# ui_conn.net
KiCad netlist of a schematic drawn in Altium Designer
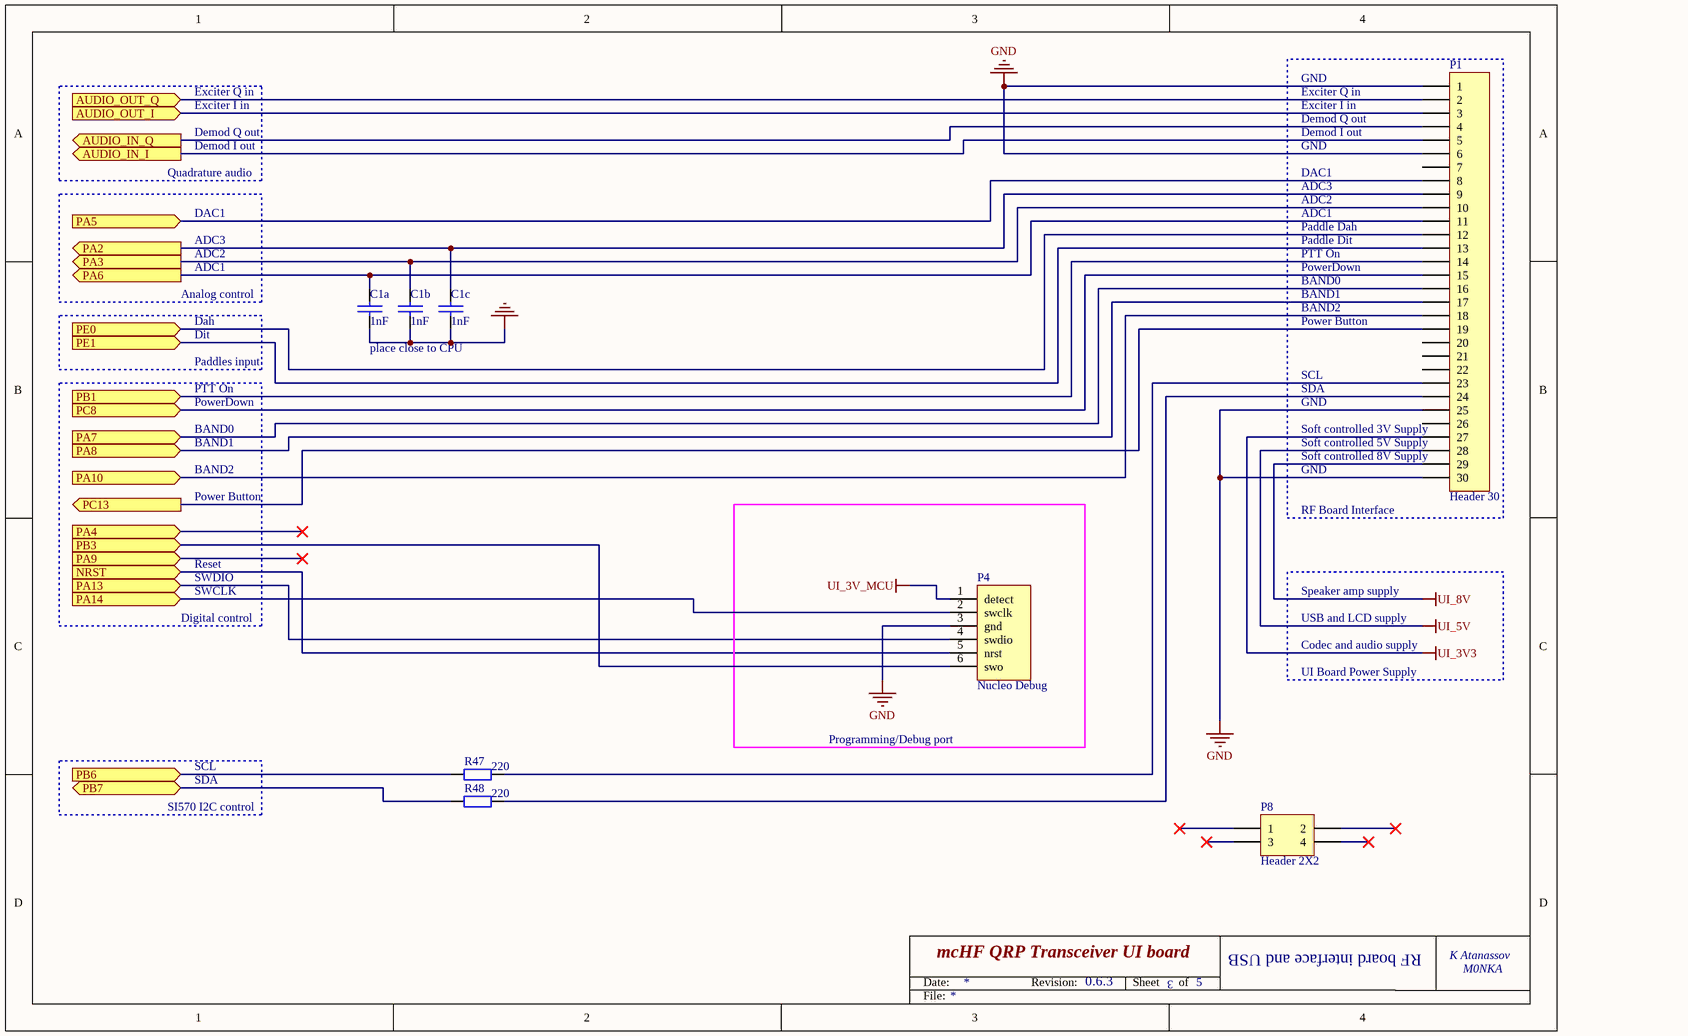
[diagram p0: ui_conn.SchDoc]

(export (version "E")
  (design (tool "Eeschema 10.0.6"))
  (components
    (comp (ref "C1a")
      (value "1nF")
      (footprint "0805-Pro")
      (description "Capacitor")
      (libsource (lib "mcHF_ui") (part "CAP"))
    )
    (comp (ref "C1b")
      (value "1nF")
      (footprint "0805-Pro")
      (description "Capacitor")
      (libsource (lib "mcHF_ui") (part "CAP"))
    )
    (comp (ref "C1c")
      (value "1nF")
      (footprint "0805-Pro")
      (description "Capacitor")
      (libsource (lib "mcHF_ui") (part "CAP"))
    )
    (comp (ref "P1")
      (value "Header 30")
      (footprint "HDR1X30")
      (description "Header, 30-Pin")
      (libsource (lib "mcHF_ui") (part "Header 30"))
    )
    (comp (ref "P4")
      (value "Nucleo Debug")
      (footprint "HDR1X6")
      (description "ST Nucleo 6 pin header")
      (libsource (lib "mcHFpro_logic") (part "Nucleo_6"))
    )
    (comp (ref "P8")
      (value "Header 2X2")
      (footprint "HDR2X2")
      (description "Header, 2-Pin, Dual row")
      (fields (field (name "PUBLISHER") "Altium Limited"))
      (libsource (lib "Miscellaneous Connectors") (part "Header 2X2"))
    )
    (comp (ref "R47")
      (value "220")
      (footprint "0805-Pro")
      (description "Resistor")
      (libsource (lib "mcHF_ui") (part "RES"))
    )
    (comp (ref "R48")
      (value "220")
      (footprint "0805-Pro")
      (description "Resistor")
      (libsource (lib "mcHF_ui") (part "RES"))
    )
  )
  (nets
    (net (code "1") (name "/AUDIO_IN_I") (class "Default")
      (node (ref "P1") (pin "5") (pinfunction "5_5") (pintype "passive"))
    )
    (net (code "2") (name "/AUDIO_IN_Q") (class "Default")
      (node (ref "P1") (pin "4") (pinfunction "4_4") (pintype "passive"))
    )
    (net (code "3") (name "/AUDIO_OUT_I") (class "Default")
      (node (ref "P1") (pin "3") (pinfunction "3_3") (pintype "passive"))
    )
    (net (code "4") (name "/AUDIO_OUT_Q") (class "Default")
      (node (ref "P1") (pin "2") (pinfunction "2_2") (pintype "passive"))
    )
    (net (code "5") (name "/NRST") (class "Default")
      (node (ref "P4") (pin "5") (pinfunction "nrst_5") (pintype "passive"))
    )
    (net (code "6") (name "/PA2") (class "Default")
      (node (ref "C1c") (pin "1") (pinfunction "1_1") (pintype "passive"))
      (node (ref "P1") (pin "9") (pinfunction "9_9") (pintype "passive"))
    )
    (net (code "7") (name "/PA3") (class "Default")
      (node (ref "C1b") (pin "1") (pinfunction "1_1") (pintype "passive"))
      (node (ref "P1") (pin "10") (pinfunction "10_10") (pintype "passive"))
    )
    (net (code "9") (name "/PA5") (class "Default")
      (node (ref "P1") (pin "8") (pinfunction "8_8") (pintype "passive"))
    )
    (net (code "10") (name "/PA6") (class "Default")
      (node (ref "C1a") (pin "1") (pinfunction "1_1") (pintype "passive"))
      (node (ref "P1") (pin "11") (pinfunction "11_11") (pintype "passive"))
    )
    (net (code "11") (name "/PA7") (class "Default")
      (node (ref "P1") (pin "16") (pinfunction "16_16") (pintype "passive"))
    )
    (net (code "12") (name "/PA8") (class "Default")
      (node (ref "P1") (pin "17") (pinfunction "17_17") (pintype "passive"))
    )
    (net (code "14") (name "/PA10") (class "Default")
      (node (ref "P1") (pin "18") (pinfunction "18_18") (pintype "passive"))
    )
    (net (code "15") (name "/PA13") (class "Default")
      (node (ref "P4") (pin "4") (pinfunction "swdio_4") (pintype "passive"))
    )
    (net (code "16") (name "/PA14") (class "Default")
      (node (ref "P4") (pin "2") (pinfunction "swclk_2") (pintype "passive"))
    )
    (net (code "17") (name "/PB1") (class "Default")
      (node (ref "P1") (pin "14") (pinfunction "14_14") (pintype "passive"))
    )
    (net (code "18") (name "/PB3") (class "Default")
      (node (ref "P4") (pin "6") (pinfunction "swo_6") (pintype "passive"))
    )
    (net (code "19") (name "/PB6") (class "Default")
      (node (ref "R47") (pin "1") (pinfunction "1_1") (pintype "passive"))
    )
    (net (code "20") (name "/PB7") (class "Default")
      (node (ref "R48") (pin "1") (pinfunction "1_1") (pintype "passive"))
    )
    (net (code "21") (name "/PC8") (class "Default")
      (node (ref "P1") (pin "15") (pinfunction "15_15") (pintype "passive"))
    )
    (net (code "22") (name "/PC13") (class "Default")
      (node (ref "P1") (pin "19") (pinfunction "19_19") (pintype "passive"))
    )
    (net (code "23") (name "/PE0") (class "Default")
      (node (ref "P1") (pin "12") (pinfunction "12_12") (pintype "passive"))
    )
    (net (code "24") (name "/PE1") (class "Default")
      (node (ref "P1") (pin "13") (pinfunction "13_13") (pintype "passive"))
    )
    (net (code "25") (name "GND") (class "Default")
      (node (ref "C1a") (pin "2") (pinfunction "2_2") (pintype "passive"))
      (node (ref "C1b") (pin "2") (pinfunction "2_2") (pintype "passive"))
      (node (ref "C1c") (pin "2") (pinfunction "2_2") (pintype "passive"))
      (node (ref "P1") (pin "1") (pinfunction "1_1") (pintype "passive"))
      (node (ref "P1") (pin "25") (pinfunction "25_25") (pintype "passive"))
      (node (ref "P1") (pin "30") (pinfunction "30_30") (pintype "passive"))
      (node (ref "P1") (pin "6") (pinfunction "6_6") (pintype "passive"))
      (node (ref "P4") (pin "3") (pinfunction "gnd_3") (pintype "passive"))
    )
    (net (code "26") (name "Net-(P1-Pad23)") (class "Default")
      (node (ref "P1") (pin "23") (pinfunction "23_23") (pintype "passive"))
      (node (ref "R47") (pin "2") (pinfunction "2_2") (pintype "passive"))
    )
    (net (code "27") (name "Net-(P1-Pad24)") (class "Default")
      (node (ref "P1") (pin "24") (pinfunction "24_24") (pintype "passive"))
      (node (ref "R48") (pin "2") (pinfunction "2_2") (pintype "passive"))
    )
    (net (code "28") (name "UI_3V3") (class "Default")
      (node (ref "P1") (pin "27") (pinfunction "27_27") (pintype "passive"))
    )
    (net (code "29") (name "UI_3V_MCU") (class "Default")
      (node (ref "P4") (pin "1") (pinfunction "detect_1") (pintype "passive"))
    )
    (net (code "30") (name "UI_5V") (class "Default")
      (node (ref "P1") (pin "28") (pinfunction "28_28") (pintype "passive"))
    )
    (net (code "31") (name "UI_8V") (class "Default")
      (node (ref "P1") (pin "29") (pinfunction "29_29") (pintype "passive"))
    )
    (net (code "32") (name "unconnected-(P1-Pad7)") (class "Default")
      (node (ref "P1") (pin "7") (pinfunction "7_7") (pintype "passive"))
    )
    (net (code "33") (name "unconnected-(P1-Pad20)") (class "Default")
      (node (ref "P1") (pin "20") (pinfunction "20_20") (pintype "passive"))
    )
    (net (code "34") (name "unconnected-(P1-Pad21)") (class "Default")
      (node (ref "P1") (pin "21") (pinfunction "21_21") (pintype "passive"))
    )
    (net (code "35") (name "unconnected-(P1-Pad22)") (class "Default")
      (node (ref "P1") (pin "22") (pinfunction "22_22") (pintype "passive"))
    )
    (net (code "36") (name "unconnected-(P1-Pad26)") (class "Default")
      (node (ref "P1") (pin "26") (pinfunction "26_26") (pintype "passive"))
    )
    (net (code "37") (name "unconnected-(P8-Pad1)") (class "Default")
      (node (ref "P8") (pin "1") (pinfunction "1_1") (pintype "passive+no_connect"))
    )
    (net (code "38") (name "unconnected-(P8-Pad2)") (class "Default")
      (node (ref "P8") (pin "2") (pinfunction "2_2") (pintype "passive+no_connect"))
    )
    (net (code "39") (name "unconnected-(P8-Pad3)") (class "Default")
      (node (ref "P8") (pin "3") (pinfunction "3_3") (pintype "passive+no_connect"))
    )
    (net (code "40") (name "unconnected-(P8-Pad4)") (class "Default")
      (node (ref "P8") (pin "4") (pinfunction "4_4") (pintype "passive+no_connect"))
    )
  )
)
